# HC-OutTemp_revA.net
KiCad netlist of a schematic drawn in EAGLE
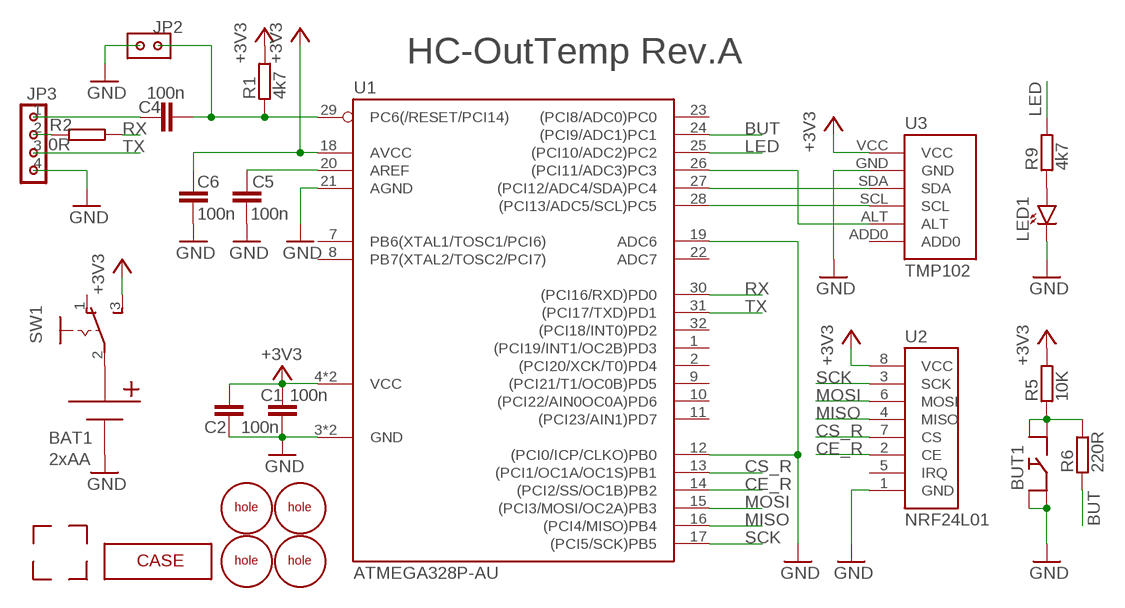
[diagram p0: schematic, sheet 1]

(export (version "E")
  (design (tool "Eeschema 10.0.6"))
  (components
    (comp (ref "BAT1")
      (value "2xAA")
      (footprint "eagle-import:2XAA_BATTERY_HOLDER")
      (libsource (lib "eagle-import") (part "BATTERY_1X'DOUBLE'"))
    )
    (comp (ref "BUT1")
      (value "BUTTON'THT'")
      (footprint "eagle-import:BUTTON")
      (libsource (lib "eagle-import") (part "BUTTON'THT'"))
    )
    (comp (ref "C1")
      (value "100n")
      (footprint "eagle-import:C0805")
      (libsource (lib "eagle-import") (part "C-CERAMIC'SMD'"))
    )
    (comp (ref "C2")
      (value "100n")
      (footprint "eagle-import:C0805")
      (libsource (lib "eagle-import") (part "C-CERAMIC'SMD'"))
    )
    (comp (ref "C4")
      (value "100n")
      (footprint "eagle-import:C0805")
      (libsource (lib "eagle-import") (part "C-CERAMIC'SMD'"))
    )
    (comp (ref "C5")
      (value "100n")
      (footprint "eagle-import:C0805")
      (libsource (lib "eagle-import") (part "C-CERAMIC'SMD'"))
    )
    (comp (ref "C6")
      (value "100n")
      (footprint "eagle-import:C0805")
      (libsource (lib "eagle-import") (part "C-CERAMIC'SMD'"))
    )
    (comp (ref "JP2")
      (value "PINHD2X1")
      (footprint "eagle-import:PINHD-2X1")
      (libsource (lib "eagle-import") (part "PINHD-2X1"))
    )
    (comp (ref "JP3")
      (value "PINHD3X1")
      (footprint "eagle-import:PINHD-4X1-90")
      (libsource (lib "eagle-import") (part "PINHD-4X1"))
    )
    (comp (ref "LED1")
      (value "LED'3MM'")
      (footprint "eagle-import:LED3MM")
      (libsource (lib "eagle-import") (part "LED'3MM'"))
    )
    (comp (ref "R1")
      (value "4k7")
      (footprint "eagle-import:R0805")
      (libsource (lib "eagle-import") (part "R'2'"))
    )
    (comp (ref "R2")
      (value "0R")
      (footprint "eagle-import:R0805")
      (libsource (lib "eagle-import") (part "R'2'"))
    )
    (comp (ref "R5")
      (value "10K")
      (footprint "eagle-import:R0805")
      (libsource (lib "eagle-import") (part "R'2'"))
    )
    (comp (ref "R6")
      (value "220R")
      (footprint "eagle-import:R0805")
      (libsource (lib "eagle-import") (part "R'2'"))
    )
    (comp (ref "R9")
      (value "4k7")
      (footprint "eagle-import:R0805")
      (libsource (lib "eagle-import") (part "R'2'"))
    )
    (comp (ref "SW1")
      (value "SWITCH_SLIDE")
      (footprint "eagle-import:SLIDE_SWITCH")
      (libsource (lib "eagle-import") (part "SWITCH_SLIDE"))
    )
    (comp (ref "U$1")
      (value "CORNER")
      (footprint "eagle-import:CORNER")
      (libsource (lib "eagle-import") (part "CORNER"))
    )
    (comp (ref "U$2")
      (value "CORNER")
      (footprint "eagle-import:CORNER")
      (libsource (lib "eagle-import") (part "CORNER"))
    )
    (comp (ref "U$3")
      (value "CORNER")
      (footprint "eagle-import:CORNER")
      (libsource (lib "eagle-import") (part "CORNER"))
    )
    (comp (ref "U$4")
      (value "CORNER")
      (footprint "eagle-import:CORNER")
      (libsource (lib "eagle-import") (part "CORNER"))
    )
    (comp (ref "U$5")
      (value "HOLE")
      (footprint "eagle-import:HOLE")
      (libsource (lib "eagle-import") (part "HOLE"))
    )
    (comp (ref "U$6")
      (value "HOLE")
      (footprint "eagle-import:HOLE")
      (libsource (lib "eagle-import") (part "HOLE"))
    )
    (comp (ref "U$7")
      (value "HOLE")
      (footprint "eagle-import:HOLE")
      (libsource (lib "eagle-import") (part "HOLE"))
    )
    (comp (ref "U$8")
      (value "HOLE")
      (footprint "eagle-import:HOLE")
      (libsource (lib "eagle-import") (part "HOLE"))
    )
    (comp (ref "U$9")
      (value "CASE'120X80X40'")
      (footprint "eagle-import:CASE-120X80X40")
      (libsource (lib "eagle-import") (part "CASE'120X80X40'"))
    )
    (comp (ref "U1")
      (value "ATMEGA328P-AU")
      (footprint "eagle-import:QFP80P900X900X120-32N")
      (libsource (lib "eagle-import") (part "ATMEGA328P-AU"))
    )
    (comp (ref "U2")
      (value "NRF24L01")
      (footprint "eagle-import:NRF24L01")
      (libsource (lib "eagle-import") (part "NRF24L01"))
    )
    (comp (ref "U3")
      (value "TMP102")
      (footprint "eagle-import:TMP102")
      (libsource (lib "eagle-import") (part "TMP102"))
    )
  )
  (nets
    (net (code "1") (name "+3V3") (class "Default")
      (node (ref "C1") (pin "2") (pinfunction "P$2_2") (pintype "bidirectional"))
      (node (ref "C2") (pin "2") (pinfunction "P$2_2") (pintype "bidirectional"))
      (node (ref "C6") (pin "2") (pinfunction "P$2_2") (pintype "bidirectional"))
      (node (ref "R1") (pin "2") (pinfunction "P$2_2") (pintype "bidirectional"))
      (node (ref "R5") (pin "2") (pinfunction "P$2_2") (pintype "bidirectional"))
      (node (ref "SW1") (pin "3") (pinfunction "S_3") (pintype "passive"))
      (node (ref "U1") (pin "18") (pinfunction "AVCC_18") (pintype "bidirectional"))
      (node (ref "U1") (pin "4") (pinfunction "VCC_4") (pintype "bidirectional"))
      (node (ref "U1") (pin "6") (pinfunction "VCC_6") (pintype "bidirectional"))
      (node (ref "U2") (pin "8") (pinfunction "VCC_8") (pintype "power_in"))
      (node (ref "U3") (pin "VCC") (pinfunction "VCC_VCC") (pintype "power_in"))
    )
    (net (code "2") (name "/BUT") (class "Default")
      (node (ref "R6") (pin "1") (pinfunction "P$1_1") (pintype "bidirectional"))
      (node (ref "U1") (pin "24") (pinfunction "(PCI9/ADC1)PC1_24") (pintype "bidirectional"))
    )
    (net (code "3") (name "/CE_R") (class "Default")
      (node (ref "U1") (pin "14") (pinfunction "(PCI2/SS/OC1B)PB2_14") (pintype "bidirectional"))
      (node (ref "U2") (pin "2") (pinfunction "CE_2") (pintype "bidirectional"))
    )
    (net (code "4") (name "/CS_R") (class "Default")
      (node (ref "U1") (pin "13") (pinfunction "(PCI1/OC1A/OC1S)PB1_13") (pintype "bidirectional"))
      (node (ref "U2") (pin "7") (pinfunction "CS_7") (pintype "bidirectional"))
    )
    (net (code "5") (name "/LED") (class "Default")
      (node (ref "R9") (pin "2") (pinfunction "P$2_2") (pintype "bidirectional"))
      (node (ref "U1") (pin "25") (pinfunction "(PCI10/ADC2)PC2_25") (pintype "bidirectional"))
    )
    (net (code "6") (name "/MISO") (class "Default")
      (node (ref "U1") (pin "16") (pinfunction "(PCI4/MISO)PB4_16") (pintype "bidirectional"))
      (node (ref "U2") (pin "4") (pinfunction "MISO_4") (pintype "bidirectional"))
    )
    (net (code "7") (name "/MOSI") (class "Default")
      (node (ref "U1") (pin "15") (pinfunction "(PCI3/MOSI/OC2A)PB3_15") (pintype "bidirectional"))
      (node (ref "U2") (pin "6") (pinfunction "MOSI_6") (pintype "bidirectional"))
    )
    (net (code "8") (name "/RX") (class "Default")
      (node (ref "R2") (pin "1") (pinfunction "P$1_1") (pintype "bidirectional"))
      (node (ref "U1") (pin "30") (pinfunction "(PCI16/RXD)PD0_30") (pintype "bidirectional"))
    )
    (net (code "9") (name "/SCK") (class "Default")
      (node (ref "U1") (pin "17") (pinfunction "(PCI5/SCK)PB5_17") (pintype "bidirectional"))
      (node (ref "U2") (pin "3") (pinfunction "SCK_3") (pintype "bidirectional"))
    )
    (net (code "10") (name "/TX") (class "Default")
      (node (ref "JP3") (pin "3") (pinfunction "3_3") (pintype "passive"))
      (node (ref "U1") (pin "31") (pinfunction "(PCI17/TXD)PD1_31") (pintype "bidirectional"))
    )
    (net (code "11") (name "GND") (class "Default")
      (node (ref "BAT1") (pin "N") (pinfunction "N_N") (pintype "power_in"))
      (node (ref "BUT1") (pin "2") (pinfunction "2_2") (pintype "bidirectional"))
      (node (ref "BUT1") (pin "4") (pinfunction "4_4") (pintype "bidirectional"))
      (node (ref "C1") (pin "1") (pinfunction "P$1_1") (pintype "bidirectional"))
      (node (ref "C2") (pin "1") (pinfunction "P$1_1") (pintype "bidirectional"))
      (node (ref "C5") (pin "2") (pinfunction "P$2_2") (pintype "bidirectional"))
      (node (ref "C6") (pin "1") (pinfunction "P$1_1") (pintype "bidirectional"))
      (node (ref "JP2") (pin "1") (pinfunction "1_1") (pintype "input"))
      (node (ref "JP3") (pin "4") (pinfunction "4_4") (pintype "passive"))
      (node (ref "LED1") (pin "K") (pinfunction "K_K") (pintype "bidirectional"))
      (node (ref "U1") (pin "12") (pinfunction "(PCI0/ICP/CLKO)PB0_12") (pintype "bidirectional"))
      (node (ref "U1") (pin "19") (pinfunction "ADC6_19") (pintype "bidirectional"))
      (node (ref "U1") (pin "21") (pinfunction "AGND_21") (pintype "bidirectional"))
      (node (ref "U1") (pin "3") (pinfunction "GND_3") (pintype "bidirectional"))
      (node (ref "U1") (pin "5") (pinfunction "GND_5") (pintype "bidirectional"))
      (node (ref "U2") (pin "1") (pinfunction "GND_1") (pintype "power_in"))
      (node (ref "U3") (pin "GND") (pinfunction "GND_GND") (pintype "power_in"))
    )
    (net (code "12") (name "Net-(C4-P$1)") (class "Default")
      (node (ref "C4") (pin "1") (pinfunction "P$1_1") (pintype "bidirectional"))
      (node (ref "JP2") (pin "2") (pinfunction "2_2") (pintype "bidirectional"))
      (node (ref "R1") (pin "1") (pinfunction "P$1_1") (pintype "bidirectional"))
      (node (ref "U1") (pin "29") (pinfunction "PC6(/RESET/PCI14)_29") (pintype "bidirectional"))
    )
    (net (code "13") (name "Net-(C4-P$2)") (class "Default")
      (node (ref "C4") (pin "2") (pinfunction "P$2_2") (pintype "bidirectional"))
      (node (ref "JP3") (pin "1") (pinfunction "1_1") (pintype "passive"))
    )
    (net (code "14") (name "Net-(C5-P$1)") (class "Default")
      (node (ref "C5") (pin "1") (pinfunction "P$1_1") (pintype "bidirectional"))
      (node (ref "U1") (pin "20") (pinfunction "AREF_20") (pintype "bidirectional"))
    )
    (net (code "15") (name "Net-(R2-P$2)") (class "Default")
      (node (ref "JP3") (pin "2") (pinfunction "2_2") (pintype "passive"))
      (node (ref "R2") (pin "2") (pinfunction "P$2_2") (pintype "bidirectional"))
    )
    (net (code "16") (name "Net-(R5-P$1)") (class "Default")
      (node (ref "BUT1") (pin "1") (pinfunction "1_1") (pintype "bidirectional"))
      (node (ref "BUT1") (pin "3") (pinfunction "3_3") (pintype "bidirectional"))
      (node (ref "R5") (pin "1") (pinfunction "P$1_1") (pintype "bidirectional"))
      (node (ref "R6") (pin "2") (pinfunction "P$2_2") (pintype "bidirectional"))
    )
    (net (code "17") (name "Net-(R9-P$1)") (class "Default")
      (node (ref "LED1") (pin "A") (pinfunction "A_A") (pintype "bidirectional"))
      (node (ref "R9") (pin "1") (pinfunction "P$1_1") (pintype "bidirectional"))
    )
    (net (code "18") (name "Net-(SW1-MIDDLE)") (class "Default")
      (node (ref "BAT1") (pin "P") (pinfunction "P_P") (pintype "power_in"))
      (node (ref "SW1") (pin "2") (pinfunction "MIDDLE_2") (pintype "passive"))
    )
    (net (code "19") (name "Net-(U1-(PCI11{slash}ADC3)PC3)") (class "Default")
      (node (ref "U1") (pin "26") (pinfunction "(PCI11/ADC3)PC3_26") (pintype "bidirectional"))
      (node (ref "U3") (pin "ALT") (pinfunction "ALT_ALT") (pintype "bidirectional"))
    )
    (net (code "20") (name "Net-(U1-(PCI12{slash}ADC4{slash}SDA)PC4)") (class "Default")
      (node (ref "U1") (pin "27") (pinfunction "(PCI12/ADC4/SDA)PC4_27") (pintype "bidirectional"))
      (node (ref "U3") (pin "SDA") (pinfunction "SDA_SDA") (pintype "bidirectional"))
    )
    (net (code "21") (name "Net-(U1-(PCI13{slash}ADC5{slash}SCL)PC5)") (class "Default")
      (node (ref "U1") (pin "28") (pinfunction "(PCI13/ADC5/SCL)PC5_28") (pintype "bidirectional"))
      (node (ref "U3") (pin "SCL") (pinfunction "SCL_SCL") (pintype "bidirectional"))
    )
    (net (code "22") (name "unconnected-(SW1-O-Pad1)") (class "Default")
      (node (ref "SW1") (pin "1") (pinfunction "O_1") (pintype "passive"))
    )
    (net (code "23") (name "unconnected-(U1-(PCI8{slash}ADC0)PC0-Pad23)") (class "Default")
      (node (ref "U1") (pin "23") (pinfunction "(PCI8/ADC0)PC0_23") (pintype "bidirectional"))
    )
    (net (code "24") (name "unconnected-(U1-(PCI18{slash}INT0)PD2-Pad32)") (class "Default")
      (node (ref "U1") (pin "32") (pinfunction "(PCI18/INT0)PD2_32") (pintype "bidirectional"))
    )
    (net (code "25") (name "unconnected-(U1-(PCI19{slash}INT1{slash}OC2B)PD3-Pad1)") (class "Default")
      (node (ref "U1") (pin "1") (pinfunction "(PCI19/INT1/OC2B)PD3_1") (pintype "bidirectional"))
    )
    (net (code "26") (name "unconnected-(U1-(PCI20{slash}XCK{slash}T0)PD4-Pad2)") (class "Default")
      (node (ref "U1") (pin "2") (pinfunction "(PCI20/XCK/T0)PD4_2") (pintype "bidirectional"))
    )
    (net (code "27") (name "unconnected-(U1-(PCI21{slash}T1{slash}OC0B)PD5-Pad9)") (class "Default")
      (node (ref "U1") (pin "9") (pinfunction "(PCI21/T1/OC0B)PD5_9") (pintype "bidirectional"))
    )
    (net (code "28") (name "unconnected-(U1-(PCI22{slash}AIN0OC0A)PD6-Pad10)") (class "Default")
      (node (ref "U1") (pin "10") (pinfunction "(PCI22/AIN0OC0A)PD6_10") (pintype "bidirectional"))
    )
    (net (code "29") (name "unconnected-(U1-(PCI23{slash}AIN1)PD7-Pad11)") (class "Default")
      (node (ref "U1") (pin "11") (pinfunction "(PCI23/AIN1)PD7_11") (pintype "bidirectional"))
    )
    (net (code "30") (name "unconnected-(U1-ADC7-Pad22)") (class "Default")
      (node (ref "U1") (pin "22") (pinfunction "ADC7_22") (pintype "bidirectional"))
    )
    (net (code "31") (name "unconnected-(U1-PB6(XTAL1{slash}TOSC1{slash}PCI6)-Pad7)") (class "Default")
      (node (ref "U1") (pin "7") (pinfunction "PB6(XTAL1/TOSC1/PCI6)_7") (pintype "bidirectional"))
    )
    (net (code "32") (name "unconnected-(U1-PB7(XTAL2{slash}TOSC2{slash}PCI7)-Pad8)") (class "Default")
      (node (ref "U1") (pin "8") (pinfunction "PB7(XTAL2/TOSC2/PCI7)_8") (pintype "bidirectional"))
    )
    (net (code "33") (name "unconnected-(U2-IRQ-Pad5)") (class "Default")
      (node (ref "U2") (pin "5") (pinfunction "IRQ_5") (pintype "bidirectional"))
    )
    (net (code "34") (name "unconnected-(U3-PadADD0)") (class "Default")
      (node (ref "U3") (pin "ADD0") (pinfunction "ADD0_ADD0") (pintype "bidirectional"))
    )
  )
)
